# uz_per_ktr_torque_box.net
KiCad netlist of a schematic drawn in Altium Designer
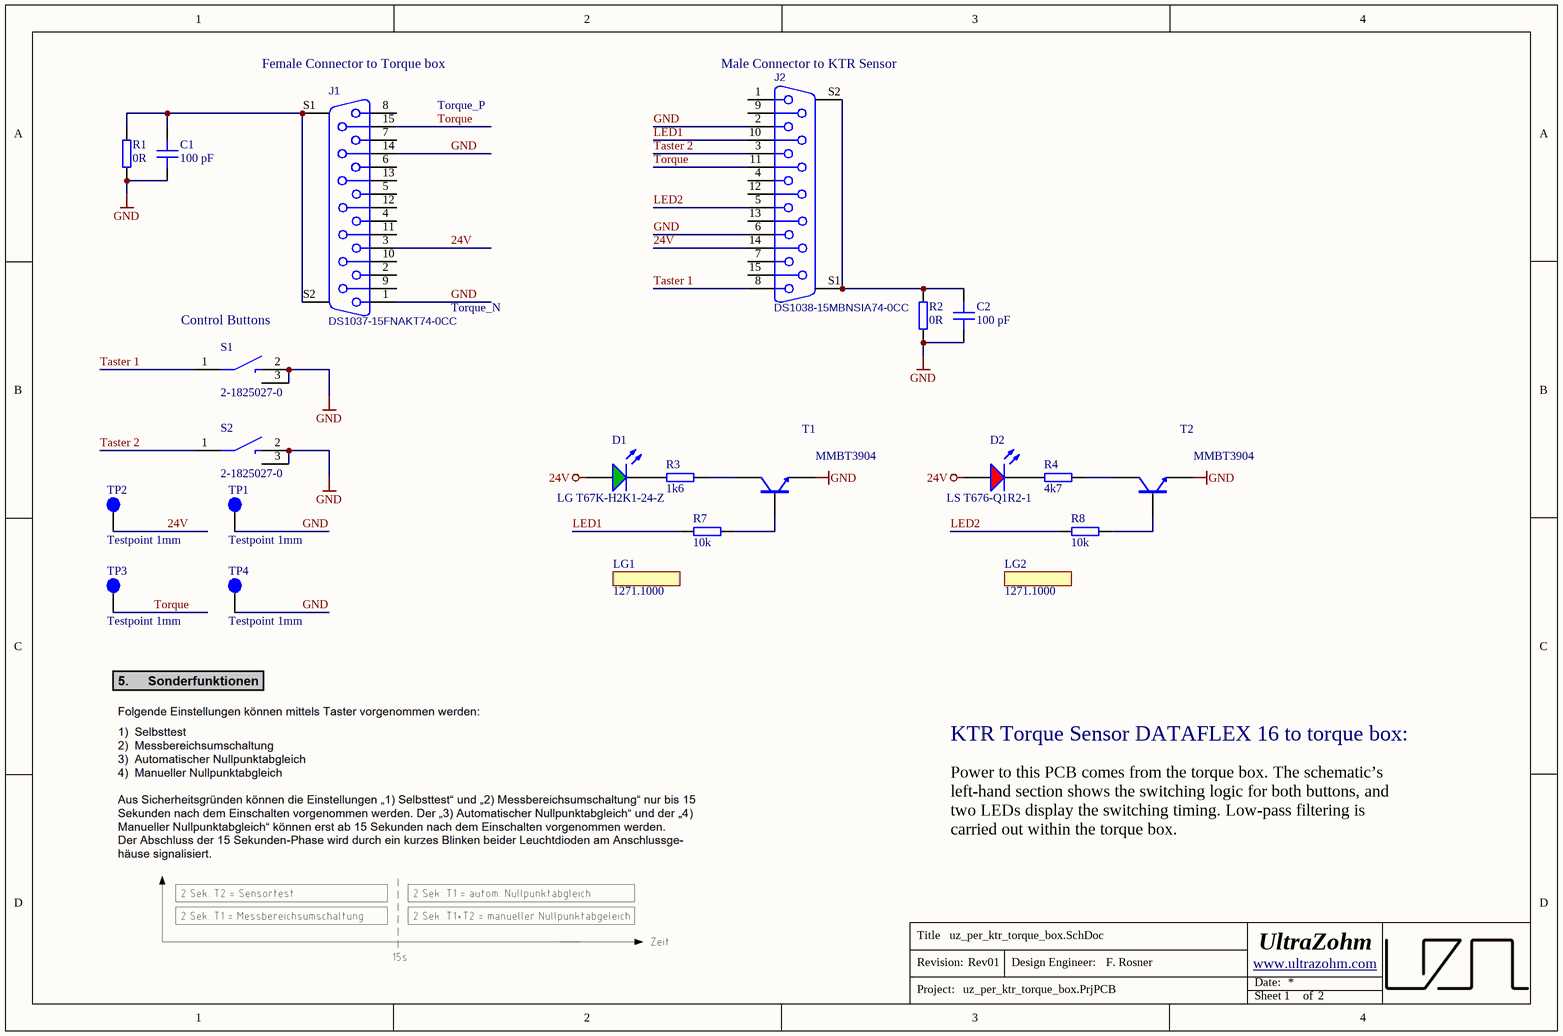
[diagram p0: uz_per_ktr_torque_box.SchDoc]

(export (version "E")
  (design (tool "Eeschema 10.0.6"))
  (components
    (comp (ref "C1")
      (value "100 pF")
      (footprint "C_1206")
      (description "Capacitor 1206, 1 kVDC, 100 pF, C0G")
      (fields
        (field (name "MANUFACTURER PART NUMBER") "885342008009")
        (field (name "MANUFACTURER") "Wuerth Elektronik")
        (field (name "CREATED FROM") "MGremer")
      )
      (libsource (lib "user") (part "Capacitor"))
    )
    (comp (ref "C2")
      (value "100 pF")
      (footprint "C_1206")
      (description "Capacitor 1206, 1 kVDC, 100 pF, C0G")
      (fields
        (field (name "MANUFACTURER PART NUMBER") "885342008009")
        (field (name "MANUFACTURER") "Wuerth Elektronik")
        (field (name "CREATED FROM") "MGremer")
      )
      (libsource (lib "user") (part "Capacitor"))
    )
    (comp (ref "D1")
      (value "LG T67K-H2K1-24-Z")
      (footprint "FP-LS_T676-Q1R2-1-Z-MFG")
      (description "Standard LEDs - SMD Green, 570nm 9mcd, 2mA")
      (fields
        (field (name "MANUFACTURER") "OSRAM Opto Semicon")
        (field (name "LCSC PART NUMBER") "C5248446")
        (field (name "CREATED FROM") "FRosner")
      )
      (libsource (lib "user") (part "LED_Green"))
    )
    (comp (ref "D2")
      (value "LS T676-Q1R2-1")
      (footprint "FP-LS_T676-Q1R2-1-Z-MFG")
      (description "Standard LEDs - SMD Super Red, 645nm 180mcd, 20mA")
      (fields
        (field (name "MANUFACTURER") "OSRAM Opto Semicon")
        (field (name "LCSC PART NUMBER") "C19360690")
        (field (name "CREATED FROM") "FRosner")
      )
      (libsource (lib "user") (part "LED_Red"))
    )
    (comp (ref "J1")
      (value "DS1037-15FNAKT74-0CC")
      (footprint "PCB - MISC - DSUB15")
      (description "15 Female D-Sub Shrouded 2 3A -40℃~+85℃ Plugin D-Sub/DVI/HDMI Connectors ROHS")
      (fields
        (field (name "BOM_SUPPLIER PART") "C2846090")
        (field (name "BOM_MANUFACTURER PART") "SUB-DRBF-607A-002")
        (field (name "CONTRIBUTOR") "LCSC")
        (field (name "CREATED FROM") "FRosner")
      )
      (libsource (lib "user") (part "SUB-DRBF-607A-002"))
    )
    (comp (ref "J2")
      (value "DS1038-15MBNSIA74-0CC")
      (footprint "DSUB15-3")
      (description "15P Male D-Sub Bend insert 3 1.5A -40℃~+105℃ Push-Pull D-Sub / VGA Connectors ROHS")
      (fields
        (field (name "BOM_SUPPLIER PART") "C2846090")
        (field (name "BOM_MANUFACTURER PART") "SUB-DRBF-607A-002")
        (field (name "CONTRIBUTOR") "LCSC")
        (field (name "CREATED FROM") "FRosner")
      )
      (libsource (lib "user") (part "SUB-DRBF-607A-002"))
    )
    (comp (ref "LG1")
      (value "1271.1000")
      (footprint "1271.1000")
      (description "Light guide, horizontal, 18.29 mm, 1 rod, round, PCB mounting, transparent")
      (fields
        (field (name "MANUFACTURER") "MENTOR")
        (field (name "LCSC PART NUMBER") "C22441102")
        (field (name "CREATED FROM") "FRosner")
      )
      (libsource (lib "user") (part "Lightguide"))
    )
    (comp (ref "LG2")
      (value "1271.1000")
      (footprint "1271.1000")
      (description "Light guide, horizontal, 18.29 mm, 1 rod, round, PCB mounting, transparent")
      (fields
        (field (name "MANUFACTURER") "MENTOR")
        (field (name "LCSC PART NUMBER") "C22441102")
        (field (name "CREATED FROM") "FRosner")
      )
      (libsource (lib "user") (part "Lightguide"))
    )
    (comp (ref "R1")
      (value "0R")
      (footprint "RES 1206_3216")
      (description "250mW Thick Film Resistors ±800ppm/℃ ±1% 0Ω 1206 Chip Resistor - Surface Mount ROHS")
      (fields
        (field (name "MANUFACTURER PART NUMBER") "1206W4F0000T5E")
        (field (name "MANUFACTURER") "UNI-ROYAL")
        (field (name "CREATED FROM") "AGeiger")
      )
      (libsource (lib "user") (part "Resistor"))
    )
    (comp (ref "R2")
      (value "0R")
      (footprint "RES 1206_3216")
      (description "250mW Thick Film Resistors ±800ppm/℃ ±1% 0Ω 1206 Chip Resistor - Surface Mount ROHS")
      (fields
        (field (name "MANUFACTURER PART NUMBER") "1206W4F0000T5E")
        (field (name "MANUFACTURER") "UNI-ROYAL")
        (field (name "CREATED FROM") "AGeiger")
      )
      (libsource (lib "user") (part "Resistor"))
    )
    (comp (ref "R3")
      (value "1k6")
      (footprint "R_1206_TE")
      (description "Generic resistor")
      (fields
        (field (name "MANUFACTURER PART NUMBER") "UZgen_R_1206_1k6")
        (field (name "MANUFACTURER") "UZgen")
        (field (name "CREATED FROM") "UZgenTool")
      )
      (libsource (lib "user") (part "RES"))
    )
    (comp (ref "R4")
      (value "4k7")
      (footprint "R_1206_TE")
      (description "Generic resistor")
      (fields
        (field (name "MANUFACTURER PART NUMBER") "UZgen_R_1206_4k7")
        (field (name "MANUFACTURER") "UZgen")
        (field (name "CREATED FROM") "UZgenTool")
      )
      (libsource (lib "user") (part "RES"))
    )
    (comp (ref "R7")
      (value "10k")
      (footprint "R_0603_TE")
      (description "Generic resistor")
      (fields
        (field (name "TOLERANCE") "1 %")
        (field (name "MANUFACTURER PART NUMBER") "UZgen_R_0603_10k")
        (field (name "CREATED FROM") "AGeiger")
      )
      (libsource (lib "user") (part "RES"))
    )
    (comp (ref "R8")
      (value "10k")
      (footprint "R_0603_TE")
      (description "Generic resistor")
      (fields
        (field (name "TOLERANCE") "1 %")
        (field (name "MANUFACTURER PART NUMBER") "UZgen_R_0603_10k")
        (field (name "CREATED FROM") "AGeiger")
      )
      (libsource (lib "user") (part "RES"))
    )
    (comp (ref "S1")
      (value "2-1825027-0")
      (footprint "2-1825027-0")
      (description "Round Button 50mA Direct Insert SPST - normally open 160gf 24V Plugin Tactile Switches ROHS")
      (fields
        (field (name "MANUFACTURER") "TE Connectivity")
        (field (name "LCSC PART NUMBER") "C590206")
        (field (name "CREATED FROM") "FRosner")
      )
      (libsource (lib "user") (part "2-1825027-0"))
    )
    (comp (ref "S2")
      (value "2-1825027-0")
      (footprint "2-1825027-0")
      (description "Round Button 50mA Direct Insert SPST - normally open 160gf 24V Plugin Tactile Switches ROHS")
      (fields
        (field (name "MANUFACTURER") "TE Connectivity")
        (field (name "LCSC PART NUMBER") "C590206")
        (field (name "CREATED FROM") "FRosner")
      )
      (libsource (lib "user") (part "2-1825027-0"))
    )
    (comp (ref "T1")
      (value "MMBT3904")
      (footprint "SOT95P280X145-3N")
      (fields
        (field (name "MANUFACTURER") "Jiangsu Changjing Electronics Technology Co., Ltd.")
        (field (name "LCSC PART NUMBER") "C20526")
        (field (name "CREATED FROM") "NDiringer")
      )
      (libsource (lib "user") (part "NPN-SOT23"))
    )
    (comp (ref "T2")
      (value "MMBT3904")
      (footprint "SOT95P280X145-3N")
      (fields
        (field (name "MANUFACTURER") "Jiangsu Changjing Electronics Technology Co., Ltd.")
        (field (name "LCSC PART NUMBER") "C20526")
        (field (name "CREATED FROM") "NDiringer")
      )
      (libsource (lib "user") (part "NPN-SOT23"))
    )
    (comp (ref "TP1")
      (value "Testpoint 1mm")
      (footprint "TP_1mm")
      (fields
        (field (name "MANUFACTURER PART NUMBER") "NULL")
        (field (name "CREATED") "2018_06_25_AGeiger")
        (field (name "CREATED FROM") "AGeiger")
      )
      (libsource (lib "user") (part "TP_1mm"))
    )
    (comp (ref "TP2")
      (value "Testpoint 1mm")
      (footprint "TP_1mm")
      (fields
        (field (name "MANUFACTURER PART NUMBER") "NULL")
        (field (name "CREATED") "2018_06_25_AGeiger")
        (field (name "CREATED FROM") "AGeiger")
      )
      (libsource (lib "user") (part "TP_1mm"))
    )
    (comp (ref "TP3")
      (value "Testpoint 1mm")
      (footprint "TP_1mm")
      (fields
        (field (name "MANUFACTURER PART NUMBER") "NULL")
        (field (name "CREATED") "2018_06_25_AGeiger")
        (field (name "CREATED FROM") "AGeiger")
      )
      (libsource (lib "user") (part "TP_1mm"))
    )
    (comp (ref "TP4")
      (value "Testpoint 1mm")
      (footprint "TP_1mm")
      (fields
        (field (name "MANUFACTURER PART NUMBER") "NULL")
        (field (name "CREATED") "2018_06_25_AGeiger")
        (field (name "CREATED FROM") "AGeiger")
      )
      (libsource (lib "user") (part "TP_1mm"))
    )
  )
  (nets
    (net (code "1") (name "/LED1") (class "Default")
      (node (ref "J2") (pin "10") (pinfunction "10_10") (pintype "passive"))
      (node (ref "R7") (pin "1") (pinfunction "1_1") (pintype "passive"))
    )
    (net (code "2") (name "/LED2") (class "Default")
      (node (ref "J2") (pin "5") (pinfunction "5_5") (pintype "passive"))
      (node (ref "R8") (pin "1") (pinfunction "1_1") (pintype "passive"))
    )
    (net (code "3") (name "/Taster 1") (class "Default")
      (node (ref "J2") (pin "8") (pinfunction "8_8") (pintype "passive"))
      (node (ref "S1") (pin "1") (pinfunction "COM1_1") (pintype "passive"))
    )
    (net (code "4") (name "/Taster 2") (class "Default")
      (node (ref "J2") (pin "3") (pinfunction "3_3") (pintype "passive"))
      (node (ref "S2") (pin "1") (pinfunction "COM1_1") (pintype "passive"))
    )
    (net (code "5") (name "/Torque") (class "Default")
      (node (ref "J1") (pin "15") (pinfunction "15_15") (pintype "passive"))
      (node (ref "J2") (pin "11") (pinfunction "11_11") (pintype "passive"))
      (node (ref "TP3") (pin "1") (pintype "passive"))
    )
    (net (code "6") (name "24V") (class "Default")
      (node (ref "D1") (pin "2") (pinfunction "A_2") (pintype "passive"))
      (node (ref "D2") (pin "2") (pinfunction "A_2") (pintype "passive"))
      (node (ref "J1") (pin "3") (pinfunction "3_3") (pintype "passive"))
      (node (ref "J2") (pin "14") (pinfunction "14_14") (pintype "passive"))
      (node (ref "TP2") (pin "1") (pintype "passive"))
    )
    (net (code "7") (name "GND") (class "Default")
      (node (ref "C1") (pin "1") (pinfunction "1_1") (pintype "passive"))
      (node (ref "C2") (pin "1") (pinfunction "1_1") (pintype "passive"))
      (node (ref "J1") (pin "1") (pinfunction "1_1") (pintype "passive"))
      (node (ref "J1") (pin "14") (pinfunction "14_14") (pintype "passive"))
      (node (ref "J2") (pin "2") (pinfunction "2_2") (pintype "passive"))
      (node (ref "J2") (pin "6") (pinfunction "6_6") (pintype "passive"))
      (node (ref "R1") (pin "1") (pinfunction "1_1") (pintype "passive"))
      (node (ref "R2") (pin "1") (pinfunction "1_1") (pintype "passive"))
      (node (ref "S1") (pin "2") (pinfunction "NO_2") (pintype "passive"))
      (node (ref "S1") (pin "3") (pinfunction "GND_3") (pintype "power_in"))
      (node (ref "S2") (pin "2") (pinfunction "NO_2") (pintype "passive"))
      (node (ref "S2") (pin "3") (pinfunction "GND_3") (pintype "power_in"))
      (node (ref "T1") (pin "2") (pinfunction "EMITTER_2") (pintype "passive"))
      (node (ref "T2") (pin "2") (pinfunction "EMITTER_2") (pintype "passive"))
      (node (ref "TP1") (pin "1") (pintype "passive"))
      (node (ref "TP4") (pin "1") (pintype "passive"))
    )
    (net (code "8") (name "Net-(D1-K)") (class "Default")
      (node (ref "D1") (pin "1") (pinfunction "K_1") (pintype "passive"))
      (node (ref "R3") (pin "1") (pinfunction "1_1") (pintype "passive"))
    )
    (net (code "9") (name "Net-(D2-K)") (class "Default")
      (node (ref "D2") (pin "1") (pinfunction "K_1") (pintype "passive"))
      (node (ref "R4") (pin "1") (pinfunction "1_1") (pintype "passive"))
    )
    (net (code "10") (name "Net-(J1-MH1)") (class "Default")
      (node (ref "C1") (pin "2") (pinfunction "2_2") (pintype "passive"))
      (node (ref "J1") (pin "S1") (pinfunction "MH1_S1") (pintype "passive"))
      (node (ref "J1") (pin "S2") (pinfunction "MH2_S2") (pintype "passive"))
      (node (ref "R1") (pin "2") (pinfunction "2_2") (pintype "passive"))
    )
    (net (code "11") (name "Net-(J2-MH1)") (class "Default")
      (node (ref "C2") (pin "2") (pinfunction "2_2") (pintype "passive"))
      (node (ref "J2") (pin "S1") (pinfunction "MH1_S1") (pintype "passive"))
      (node (ref "J2") (pin "S2") (pinfunction "MH2_S2") (pintype "passive"))
      (node (ref "R2") (pin "2") (pinfunction "2_2") (pintype "passive"))
    )
    (net (code "12") (name "Net-(T1-BASIS)") (class "Default")
      (node (ref "R7") (pin "2") (pinfunction "2_2") (pintype "passive"))
      (node (ref "T1") (pin "1") (pinfunction "BASIS_1") (pintype "passive"))
    )
    (net (code "13") (name "Net-(T1-COLLECTOR)") (class "Default")
      (node (ref "R3") (pin "2") (pinfunction "2_2") (pintype "passive"))
      (node (ref "T1") (pin "3") (pinfunction "COLLECTOR_3") (pintype "passive"))
    )
    (net (code "14") (name "Net-(T2-BASIS)") (class "Default")
      (node (ref "R8") (pin "2") (pinfunction "2_2") (pintype "passive"))
      (node (ref "T2") (pin "1") (pinfunction "BASIS_1") (pintype "passive"))
    )
    (net (code "15") (name "Net-(T2-COLLECTOR)") (class "Default")
      (node (ref "R4") (pin "2") (pinfunction "2_2") (pintype "passive"))
      (node (ref "T2") (pin "3") (pinfunction "COLLECTOR_3") (pintype "passive"))
    )
    (net (code "16") (name "unconnected-(J1-Pad2)") (class "Default")
      (node (ref "J1") (pin "2") (pinfunction "2_2") (pintype "passive"))
    )
    (net (code "17") (name "unconnected-(J1-Pad4)") (class "Default")
      (node (ref "J1") (pin "4") (pinfunction "4_4") (pintype "passive"))
    )
    (net (code "18") (name "unconnected-(J1-Pad5)") (class "Default")
      (node (ref "J1") (pin "5") (pinfunction "5_5") (pintype "passive"))
    )
    (net (code "19") (name "unconnected-(J1-Pad6)") (class "Default")
      (node (ref "J1") (pin "6") (pinfunction "6_6") (pintype "passive"))
    )
    (net (code "20") (name "unconnected-(J1-Pad7)") (class "Default")
      (node (ref "J1") (pin "7") (pinfunction "7_7") (pintype "passive"))
    )
    (net (code "21") (name "unconnected-(J1-Pad8)") (class "Default")
      (node (ref "J1") (pin "8") (pinfunction "8_8") (pintype "passive"))
    )
    (net (code "22") (name "unconnected-(J1-Pad9)") (class "Default")
      (node (ref "J1") (pin "9") (pinfunction "9_9") (pintype "passive"))
    )
    (net (code "23") (name "unconnected-(J1-Pad10)") (class "Default")
      (node (ref "J1") (pin "10") (pinfunction "10_10") (pintype "passive"))
    )
    (net (code "24") (name "unconnected-(J1-Pad11)") (class "Default")
      (node (ref "J1") (pin "11") (pinfunction "11_11") (pintype "passive"))
    )
    (net (code "25") (name "unconnected-(J1-Pad12)") (class "Default")
      (node (ref "J1") (pin "12") (pinfunction "12_12") (pintype "passive"))
    )
    (net (code "26") (name "unconnected-(J1-Pad13)") (class "Default")
      (node (ref "J1") (pin "13") (pinfunction "13_13") (pintype "passive"))
    )
    (net (code "27") (name "unconnected-(J2-Pad1)") (class "Default")
      (node (ref "J2") (pin "1") (pinfunction "1_1") (pintype "passive"))
    )
    (net (code "28") (name "unconnected-(J2-Pad4)") (class "Default")
      (node (ref "J2") (pin "4") (pinfunction "4_4") (pintype "passive"))
    )
    (net (code "29") (name "unconnected-(J2-Pad7)") (class "Default")
      (node (ref "J2") (pin "7") (pinfunction "7_7") (pintype "passive"))
    )
    (net (code "30") (name "unconnected-(J2-Pad9)") (class "Default")
      (node (ref "J2") (pin "9") (pinfunction "9_9") (pintype "passive"))
    )
    (net (code "31") (name "unconnected-(J2-Pad12)") (class "Default")
      (node (ref "J2") (pin "12") (pinfunction "12_12") (pintype "passive"))
    )
    (net (code "32") (name "unconnected-(J2-Pad13)") (class "Default")
      (node (ref "J2") (pin "13") (pinfunction "13_13") (pintype "passive"))
    )
    (net (code "33") (name "unconnected-(J2-Pad15)") (class "Default")
      (node (ref "J2") (pin "15") (pinfunction "15_15") (pintype "passive"))
    )
  )
)
